# Audio.net
KiCad netlist of a schematic drawn in Altium Designer
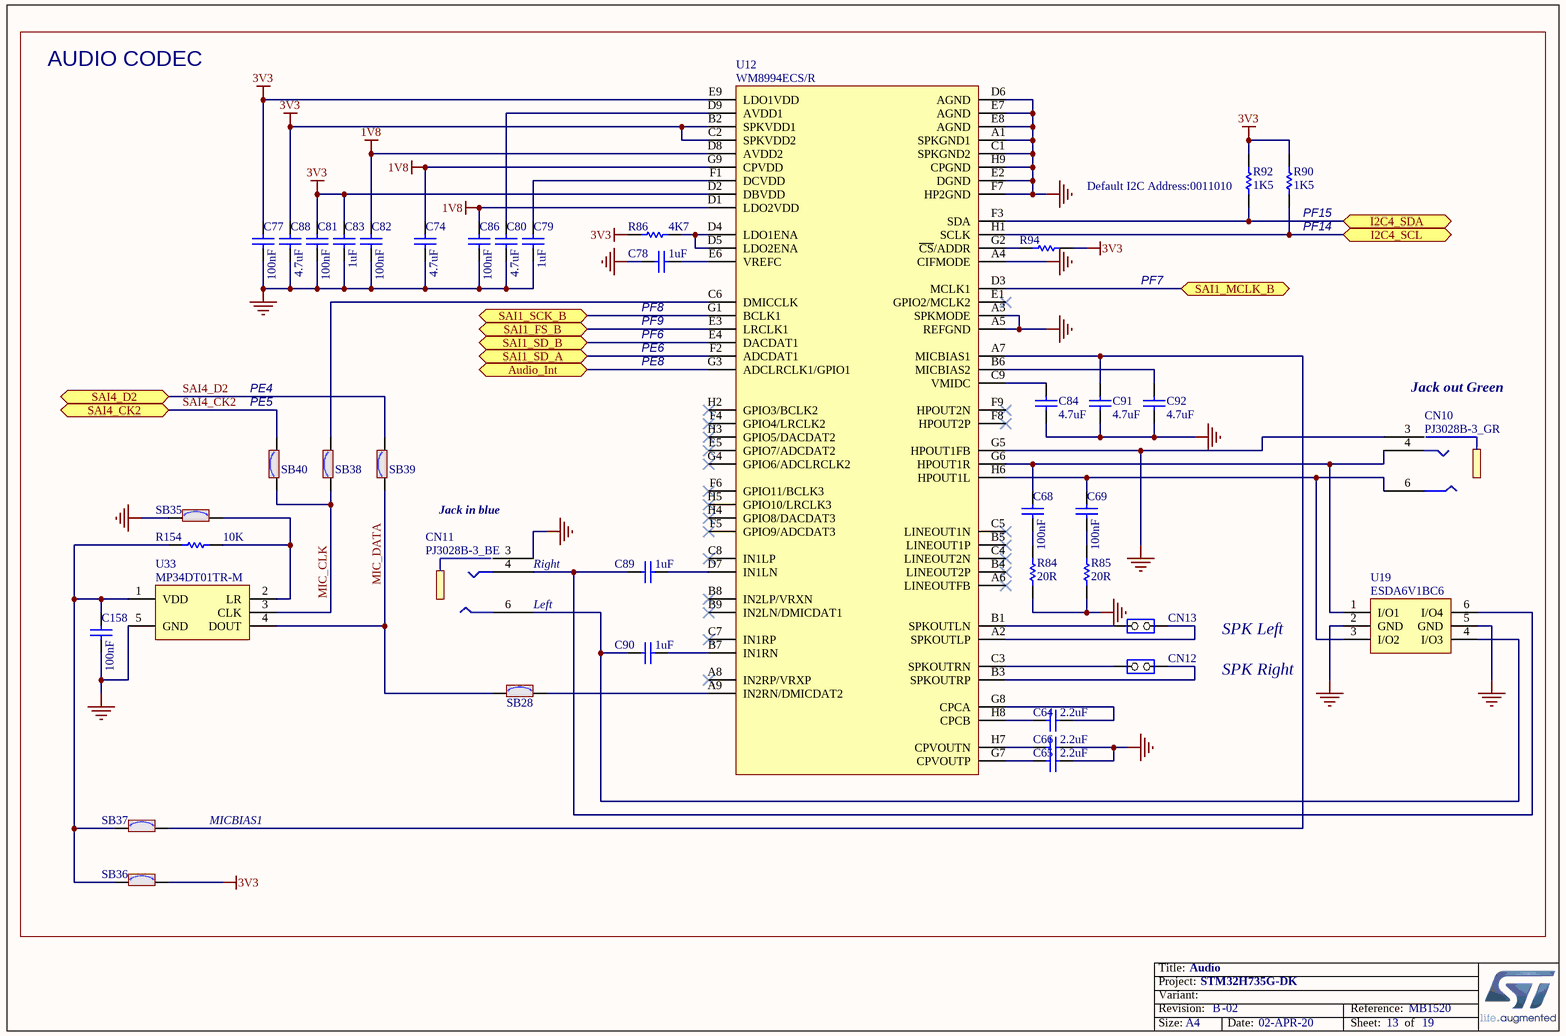
[diagram p0: Audio.SchDoc]

(export (version "E")
  (design (tool "Eeschema 10.0.6"))
  (components
    (comp (ref "C64")
      (value "2.2uF")
      (footprint "C0603")
      (description "Capacitor, MLCC, 2.2uF, 10V, X5R, 10%, 0603, T=0,8mm")
      (fields
        (field (name "INTERNAL_PART_NUMBER") "MCD-00012")
        (field (name "MANUFACTURER_PART_NUMBER") "CC0603KRX5R6BB225")
        (field (name "PROVIDED_BY") "SUBCO")
      )
      (libsource (lib "MCD_PARTS_database") (part "Capacitor"))
    )
    (comp (ref "C65")
      (value "2.2uF")
      (footprint "C0603")
      (description "Capacitor, MLCC, 2.2uF, 10V, X5R, 10%, 0603, T=0,8mm")
      (fields
        (field (name "INTERNAL_PART_NUMBER") "MCD-00012")
        (field (name "MANUFACTURER_PART_NUMBER") "CC0603KRX5R6BB225")
        (field (name "PROVIDED_BY") "SUBCO")
      )
      (libsource (lib "MCD_PARTS_database") (part "Capacitor"))
    )
    (comp (ref "C66")
      (value "2.2uF")
      (footprint "C0603")
      (description "Capacitor, MLCC, 2.2uF, 10V, X5R, 10%, 0603, T=0,8mm")
      (fields
        (field (name "INTERNAL_PART_NUMBER") "MCD-00012")
        (field (name "MANUFACTURER_PART_NUMBER") "CC0603KRX5R6BB225")
        (field (name "PROVIDED_BY") "SUBCO")
      )
      (libsource (lib "MCD_PARTS_database") (part "Capacitor"))
    )
    (comp (ref "C68")
      (value "100nF")
      (footprint "C0402")
      (description "Capacitor, MLCC, 100nF, 16V, X7R, 10%, 0402, T=0,5mm")
      (fields
        (field (name "INTERNAL_PART_NUMBER") "MCD-00102")
        (field (name "MANUFACTURER_PART_NUMBER") "CC0402KRX7R7BB104")
        (field (name "PROVIDED_BY") "SUBCO")
      )
      (libsource (lib "MCD_PARTS_database") (part "Capacitor"))
    )
    (comp (ref "C69")
      (value "100nF")
      (footprint "C0402")
      (description "Capacitor, MLCC, 100nF, 16V, X7R, 10%, 0402, T=0,5mm")
      (fields
        (field (name "INTERNAL_PART_NUMBER") "MCD-00102")
        (field (name "MANUFACTURER_PART_NUMBER") "CC0402KRX7R7BB104")
        (field (name "PROVIDED_BY") "SUBCO")
      )
      (libsource (lib "MCD_PARTS_database") (part "Capacitor"))
    )
    (comp (ref "C74")
      (value "4.7uF")
      (footprint "C0603")
      (description "Capacitor, MLCC, 4.7uF, 16V, X5R, 10%, 0603, T=0.8mm")
      (fields
        (field (name "INTERNAL_PART_NUMBER") "MCD-00009")
        (field (name "MANUFACTURER_PART_NUMBER") "CC0603KRX5R7BB475")
        (field (name "PROVIDED_BY") "SUBCO")
      )
      (libsource (lib "MCD_PARTS_database") (part "Capacitor"))
    )
    (comp (ref "C77")
      (value "100nF")
      (footprint "C0402")
      (description "Capacitor, MLCC, 100nF, 16V, X7R, 10%, 0402, T=0,5mm")
      (fields
        (field (name "INTERNAL_PART_NUMBER") "MCD-00102")
        (field (name "MANUFACTURER_PART_NUMBER") "CC0402KRX7R7BB104")
        (field (name "PROVIDED_BY") "SUBCO")
      )
      (libsource (lib "MCD_PARTS_database") (part "Capacitor"))
    )
    (comp (ref "C78")
      (value "1uF")
      (footprint "C0603")
      (description "Capacitor, MLCC, 1uF, 16V, X5R, 10%, 0603, T=0,8mm")
      (fields
        (field (name "INTERNAL_PART_NUMBER") "MCD-00010")
        (field (name "MANUFACTURER_PART_NUMBER") "CC0603KRX5R7BB105")
        (field (name "PROVIDED_BY") "SUBCO")
      )
      (libsource (lib "MCD_PARTS_database") (part "Capacitor"))
    )
    (comp (ref "C79")
      (value "1uF")
      (footprint "C0603")
      (description "Capacitor, MLCC, 1uF, 16V, X5R, 10%, 0603, T=0,8mm")
      (fields
        (field (name "INTERNAL_PART_NUMBER") "MCD-00010")
        (field (name "MANUFACTURER_PART_NUMBER") "CC0603KRX5R7BB105")
        (field (name "PROVIDED_BY") "SUBCO")
      )
      (libsource (lib "MCD_PARTS_database") (part "Capacitor"))
    )
    (comp (ref "C80")
      (value "4.7uF")
      (footprint "C0603")
      (description "Capacitor, MLCC, 4.7uF, 16V, X5R, 10%, 0603, T=0.8mm")
      (fields
        (field (name "INTERNAL_PART_NUMBER") "MCD-00009")
        (field (name "MANUFACTURER_PART_NUMBER") "CC0603KRX5R7BB475")
        (field (name "PROVIDED_BY") "SUBCO")
      )
      (libsource (lib "MCD_PARTS_database") (part "Capacitor"))
    )
    (comp (ref "C81")
      (value "100nF")
      (footprint "C0402")
      (description "Capacitor, MLCC, 100nF, 16V, X7R, 10%, 0402, T=0,5mm")
      (fields
        (field (name "INTERNAL_PART_NUMBER") "MCD-00102")
        (field (name "MANUFACTURER_PART_NUMBER") "CC0402KRX7R7BB104")
        (field (name "PROVIDED_BY") "SUBCO")
      )
      (libsource (lib "MCD_PARTS_database") (part "Capacitor"))
    )
    (comp (ref "C82")
      (value "100nF")
      (footprint "C0402")
      (description "Capacitor, MLCC, 100nF, 16V, X7R, 10%, 0402, T=0,5mm")
      (fields
        (field (name "INTERNAL_PART_NUMBER") "MCD-00102")
        (field (name "MANUFACTURER_PART_NUMBER") "CC0402KRX7R7BB104")
        (field (name "PROVIDED_BY") "SUBCO")
      )
      (libsource (lib "MCD_PARTS_database") (part "Capacitor"))
    )
    (comp (ref "C83")
      (value "1uF")
      (footprint "C0603")
      (description "Capacitor, MLCC, 1uF, 16V, X5R, 10%, 0603, T=0,8mm")
      (fields
        (field (name "INTERNAL_PART_NUMBER") "MCD-00010")
        (field (name "MANUFACTURER_PART_NUMBER") "CC0603KRX5R7BB105")
        (field (name "PROVIDED_BY") "SUBCO")
      )
      (libsource (lib "MCD_PARTS_database") (part "Capacitor"))
    )
    (comp (ref "C84")
      (value "4.7uF")
      (footprint "C0603")
      (description "Capacitor, MLCC, 4.7uF, 16V, X5R, 10%, 0603, T=0.8mm")
      (fields
        (field (name "INTERNAL_PART_NUMBER") "MCD-00009")
        (field (name "MANUFACTURER_PART_NUMBER") "CC0603KRX5R7BB475")
        (field (name "PROVIDED_BY") "SUBCO")
      )
      (libsource (lib "MCD_PARTS_database") (part "Capacitor"))
    )
    (comp (ref "C86")
      (value "100nF")
      (footprint "C0402")
      (description "Capacitor, MLCC, 100nF, 16V, X7R, 10%, 0402, T=0,5mm")
      (fields
        (field (name "INTERNAL_PART_NUMBER") "MCD-00102")
        (field (name "MANUFACTURER_PART_NUMBER") "CC0402KRX7R7BB104")
        (field (name "PROVIDED_BY") "SUBCO")
      )
      (libsource (lib "MCD_PARTS_database") (part "Capacitor"))
    )
    (comp (ref "C88")
      (value "4.7uF")
      (footprint "C0603")
      (description "Capacitor, MLCC, 4.7uF, 16V, X5R, 10%, 0603, T=0.8mm")
      (fields
        (field (name "INTERNAL_PART_NUMBER") "MCD-00009")
        (field (name "MANUFACTURER_PART_NUMBER") "CC0603KRX5R7BB475")
        (field (name "PROVIDED_BY") "SUBCO")
      )
      (libsource (lib "MCD_PARTS_database") (part "Capacitor"))
    )
    (comp (ref "C89")
      (value "1uF")
      (footprint "C0603")
      (description "Capacitor, MLCC, 1uF, 16V, X5R, 10%, 0603, T=0,8mm")
      (fields
        (field (name "INTERNAL_PART_NUMBER") "MCD-00010")
        (field (name "MANUFACTURER_PART_NUMBER") "CC0603KRX5R7BB105")
        (field (name "PROVIDED_BY") "SUBCO")
      )
      (libsource (lib "MCD_PARTS_database") (part "Capacitor"))
    )
    (comp (ref "C90")
      (value "1uF")
      (footprint "C0603")
      (description "Capacitor, MLCC, 1uF, 16V, X5R, 10%, 0603, T=0,8mm")
      (fields
        (field (name "INTERNAL_PART_NUMBER") "MCD-00010")
        (field (name "MANUFACTURER_PART_NUMBER") "CC0603KRX5R7BB105")
        (field (name "PROVIDED_BY") "SUBCO")
      )
      (libsource (lib "MCD_PARTS_database") (part "Capacitor"))
    )
    (comp (ref "C91")
      (value "4.7uF")
      (footprint "C0603")
      (description "Capacitor, MLCC, 4.7uF, 16V, X5R, 10%, 0603, T=0.8mm")
      (fields
        (field (name "INTERNAL_PART_NUMBER") "MCD-00009")
        (field (name "MANUFACTURER_PART_NUMBER") "CC0603KRX5R7BB475")
        (field (name "PROVIDED_BY") "SUBCO")
      )
      (libsource (lib "MCD_PARTS_database") (part "Capacitor"))
    )
    (comp (ref "C92")
      (value "4.7uF")
      (footprint "C0603")
      (description "Capacitor, MLCC, 4.7uF, 16V, X5R, 10%, 0603, T=0.8mm")
      (fields
        (field (name "INTERNAL_PART_NUMBER") "MCD-00009")
        (field (name "MANUFACTURER_PART_NUMBER") "CC0603KRX5R7BB475")
        (field (name "PROVIDED_BY") "SUBCO")
      )
      (libsource (lib "MCD_PARTS_database") (part "Capacitor"))
    )
    (comp (ref "C158")
      (value "100nF")
      (footprint "C0402")
      (description "Capacitor, MLCC, 100nF, 16V, X7R, 10%, 0402, T=0,5mm")
      (fields
        (field (name "INTERNAL_PART_NUMBER") "MCD-00102")
        (field (name "MANUFACTURER_PART_NUMBER") "CC0402KRX7R7BB104")
        (field (name "PROVIDED_BY") "SUBCO")
      )
      (libsource (lib "MCD_PARTS_database") (part "Capacitor"))
    )
    (comp (ref "CN10")
      (value "PJ3028B-3_GR")
      (footprint "CON_PHONE-JACK-3P5_HY_PJ3028B")
      (description "Connector Jack socket Stereo 3.5mm, 3 pins, RA, SMT, Green (Line output)")
      (fields
        (field (name "INTERNAL_PART_NUMBER") "MCD-00018")
        (field (name "MANUFACTURER") "QIAOD")
        (field (name "PROVIDED_BY") "SUBCO")
      )
      (libsource (lib "MCD_PARTS_database") (part "Jack_PJ3028B-3_3P"))
    )
    (comp (ref "CN11")
      (value "PJ3028B-3_BE")
      (footprint "CON_PHONE-JACK-3P5_HY_PJ3028B")
      (description "Connector Jack socket Stereo 3.5mm, 3 pins, RA, SMT, Blue (Line input)")
      (fields
        (field (name "INTERNAL_PART_NUMBER") "MCD-00682")
        (field (name "MANUFACTURER") "QIAOD")
        (field (name "PROVIDED_BY") "SUBCO")
      )
      (libsource (lib "") (part "Jack_PJ3028B-3_3P_1"))
    )
    (comp (ref "CN12")
      (value "Jumper_Header 2x1")
      (footprint "CON_SAMTEC_TSW-102-07-G-S")
      (description "Header, 2x1, 2,54mm, VR, TH, Height 5.84mm/2.54mm")
      (fields
        (field (name "INTERNAL_PART_NUMBER") "MCD-00045")
        (field (name "MANUFACTURER_PART_NUMBER") "TSW-102-07-x-S")
        (field (name "PROVIDED_BY") "SUBCO")
      )
      (libsource (lib "MCD_PARTS_database") (part "Jumper_Header 2x1"))
    )
    (comp (ref "CN13")
      (value "Jumper_Header 2x1")
      (footprint "CON_SAMTEC_TSW-102-07-G-S")
      (description "Header, 2x1, 2,54mm, VR, TH, Height 5.84mm/2.54mm")
      (fields
        (field (name "INTERNAL_PART_NUMBER") "MCD-00045")
        (field (name "MANUFACTURER_PART_NUMBER") "TSW-102-07-x-S")
        (field (name "PROVIDED_BY") "SUBCO")
      )
      (libsource (lib "MCD_PARTS_database") (part "Jumper_Header 2x1"))
    )
    (comp (ref "R84")
      (value "20R")
      (footprint "R0603")
      (description "Resistor,20R,0603,1%,1/10W")
      (fields
        (field (name "INTERNAL_PART_NUMBER") "MCD-00345")
        (field (name "MANUFACTURER_PART_NUMBER") "RC0603FR-0720RL")
        (field (name "PROVIDED_BY") "SUBCO")
      )
      (libsource (lib "MCD_PARTS_database") (part "Resistor"))
    )
    (comp (ref "R85")
      (value "20R")
      (footprint "R0603")
      (description "Resistor,20R,0603,1%,1/10W")
      (fields
        (field (name "INTERNAL_PART_NUMBER") "MCD-00345")
        (field (name "MANUFACTURER_PART_NUMBER") "RC0603FR-0720RL")
        (field (name "PROVIDED_BY") "SUBCO")
      )
      (libsource (lib "MCD_PARTS_database") (part "Resistor"))
    )
    (comp (ref "R86")
      (value "4K7")
      (footprint "R0603")
      (description "Resistor,4K7,0603,1%,1/10W")
      (fields
        (field (name "INTERNAL_PART_NUMBER") "MCD-00219")
        (field (name "MANUFACTURER_PART_NUMBER") "RC0603FR-074K7L")
        (field (name "PROVIDED_BY") "SUBCO")
      )
      (libsource (lib "MCD_PARTS_database") (part "Resistor"))
    )
    (comp (ref "R90")
      (value "1K5")
      (footprint "R0402")
      (description "Resistor,1K5,0402,1%,1/16W")
      (fields
        (field (name "INTERNAL_PART_NUMBER") "MCD-00068")
        (field (name "MANUFACTURER_PART_NUMBER") "RC0402FR-071K5L")
        (field (name "PROVIDED_BY") "SUBCO")
      )
      (libsource (lib "MCD_PARTS_database") (part "Resistor"))
    )
    (comp (ref "R92")
      (value "1K5")
      (footprint "R0402")
      (description "Resistor,1K5,0402,1%,1/16W")
      (fields
        (field (name "INTERNAL_PART_NUMBER") "MCD-00068")
        (field (name "MANUFACTURER_PART_NUMBER") "RC0402FR-071K5L")
        (field (name "PROVIDED_BY") "SUBCO")
      )
      (libsource (lib "MCD_PARTS_database") (part "Resistor"))
    )
    (comp (ref "R94")
      (value "Resistor")
      (footprint "R0402")
      (description "Resistor,10K,0402,1%,1/16W")
      (fields
        (field (name "INTERNAL_PART_NUMBER") "MCD-00053")
        (field (name "MANUFACTURER_PART_NUMBER") "RC0402FR-0710KL")
        (field (name "PROVIDED_BY") "SUBCO")
      )
      (libsource (lib "MCD_PARTS_database") (part "Resistor"))
    )
    (comp (ref "R154")
      (value "10K")
      (footprint "R0402")
      (description "Resistor,10K,0402,1%,1/16W")
      (fields
        (field (name "INTERNAL_PART_NUMBER") "MCD-00053")
        (field (name "MANUFACTURER_PART_NUMBER") "RC0402FR-0710KL")
        (field (name "PROVIDED_BY") "SUBCO")
      )
      (libsource (lib "MCD_PARTS_database") (part "Resistor"))
    )
    (comp (ref "SB28")
      (value "SB_ON")
      (footprint "SOLDER-BRIDGE_R0603-0R")
      (description "Solder Bridge ON")
      (fields
        (field (name "INTERNAL_PART_NUMBER") "MCD-00071")
        (field (name "MANUFACTURER_PART_NUMBER") "RC0603JR-070RL")
        (field (name "PROVIDED_BY") "SUBCO")
      )
      (libsource (lib "MCD_PARTS_database") (part "SB_ON"))
    )
    (comp (ref "SB35")
      (value "SB_ON")
      (footprint "SOLDER-BRIDGE_R0603-0R")
      (description "Solder Bridge ON")
      (fields
        (field (name "INTERNAL_PART_NUMBER") "MCD-00071")
        (field (name "MANUFACTURER_PART_NUMBER") "RC0603JR-070RL")
        (field (name "PROVIDED_BY") "SUBCO")
      )
      (libsource (lib "MCD_PARTS_database") (part "SB_ON"))
    )
    (comp (ref "SB36")
      (value "SB_ON")
      (footprint "SOLDER-BRIDGE_R0603-0R")
      (description "Solder Bridge ON")
      (fields
        (field (name "INTERNAL_PART_NUMBER") "MCD-00071")
        (field (name "MANUFACTURER_PART_NUMBER") "RC0603JR-070RL")
        (field (name "PROVIDED_BY") "SUBCO")
      )
      (libsource (lib "MCD_PARTS_database") (part "SB_ON"))
    )
    (comp (ref "SB37")
      (value "SB_ON")
      (footprint "SOLDER-BRIDGE_R0603-0R")
      (description "Solder Bridge ON")
      (fields
        (field (name "INTERNAL_PART_NUMBER") "MCD-00071")
        (field (name "MANUFACTURER_PART_NUMBER") "RC0603JR-070RL")
        (field (name "PROVIDED_BY") "SUBCO")
      )
      (libsource (lib "MCD_PARTS_database") (part "SB_ON"))
    )
    (comp (ref "SB38")
      (value "SB_ON")
      (footprint "SOLDER-BRIDGE_R0603-0R")
      (description "Solder Bridge ON")
      (fields
        (field (name "INTERNAL_PART_NUMBER") "MCD-00071")
        (field (name "MANUFACTURER_PART_NUMBER") "RC0603JR-070RL")
        (field (name "PROVIDED_BY") "SUBCO")
      )
      (libsource (lib "") (part "SB_ON_1"))
    )
    (comp (ref "SB39")
      (value "SB_ON")
      (footprint "SOLDER-BRIDGE_R0603-0R")
      (description "Solder Bridge ON")
      (fields
        (field (name "INTERNAL_PART_NUMBER") "MCD-00071")
        (field (name "MANUFACTURER_PART_NUMBER") "RC0603JR-070RL")
        (field (name "PROVIDED_BY") "SUBCO")
      )
      (libsource (lib "") (part "SB_ON_1"))
    )
    (comp (ref "SB40")
      (value "SB_ON")
      (footprint "SOLDER-BRIDGE_R0603-0R")
      (description "Solder Bridge ON")
      (fields
        (field (name "INTERNAL_PART_NUMBER") "MCD-00071")
        (field (name "MANUFACTURER_PART_NUMBER") "RC0603JR-070RL")
        (field (name "PROVIDED_BY") "SUBCO")
      )
      (libsource (lib "") (part "SB_ON_1"))
    )
    (comp (ref "U12")
      (value "WM8994ECS/R")
      (footprint "ICC_W-CSP-BGA72_4P511X4P023_P050")
      (description "Multi-Channel Audio Hub CODEC for Smartphones")
      (fields
        (field (name "INTERNAL_PART_NUMBER") "MCD-00079")
        (field (name "MANUFACTURER") "CIRRUS LOGIC")
        (field (name "PROVIDED_BY") "SUBCO")
      )
      (libsource (lib "MCD_PARTS_database") (part "WM8994ECS/R"))
    )
    (comp (ref "U19")
      (value "ESDA6V1BC6")
      (footprint "ESD_SOT23-6L")
      (description "Quad Bidir ESD protection")
      (fields
        (field (name "INTERNAL_PART_NUMBER") "MCD-00247")
        (field (name "MANUFACTURER") "STMICROELECTRONICS")
        (field (name "PROVIDED_BY") "SUBCO with ST control")
      )
      (libsource (lib "MCD_PARTS_database") (part "ESDA6V1BC6"))
    )
    (comp (ref "U33")
      (value "MP34DT01TR-M")
      (footprint "MIC_HCLGA_3X4X1_4LD")
      (description "MEMS audio sensor, omnidirectional digital microphone")
      (fields
        (field (name "INTERNAL_PART_NUMBER") "MCD-00081")
        (field (name "MANUFACTURER") "STMICROELECTRONICS")
        (field (name "PROVIDED_BY") "SUBCO with ST control")
      )
      (libsource (lib "MCD_PARTS_database") (part "MP34DT01TR-M"))
    )
  )
  (nets
    (net (code "1") (name "/Audio_Int") (class "Default")
      (node (ref "U12") (pin "G3") (pinfunction "ADCLRCLK1/GPIO1_G3") (pintype "passive"))
    )
    (net (code "2") (name "/I2C4_SCL") (class "Default")
      (node (ref "R90") (pin "1") (pinfunction "1_1") (pintype "passive"))
      (node (ref "U12") (pin "H1") (pinfunction "SCLK_H1") (pintype "passive"))
    )
    (net (code "3") (name "/I2C4_SDA") (class "Default")
      (node (ref "R92") (pin "1") (pinfunction "1_1") (pintype "passive"))
      (node (ref "U12") (pin "F3") (pinfunction "SDA_F3") (pintype "passive"))
    )
    (net (code "4") (name "/MIC_CLK") (class "Default")
      (node (ref "SB38") (pin "1") (pinfunction "1_1") (pintype "passive"))
      (node (ref "SB40") (pin "1") (pinfunction "1_1") (pintype "passive"))
      (node (ref "U33") (pin "3") (pinfunction "CLK_3") (pintype "passive"))
    )
    (net (code "5") (name "/MIC_DATA") (class "Default")
      (node (ref "SB28") (pin "1") (pinfunction "1_1") (pintype "passive"))
      (node (ref "SB39") (pin "1") (pinfunction "1_1") (pintype "passive"))
      (node (ref "U33") (pin "4") (pinfunction "DOUT_4") (pintype "passive"))
    )
    (net (code "6") (name "/SAI1_FS_B") (class "Default")
      (node (ref "U12") (pin "E3") (pinfunction "LRCLK1_E3") (pintype "passive"))
    )
    (net (code "7") (name "/SAI1_MCLK_B") (class "Default")
      (node (ref "U12") (pin "D3") (pinfunction "MCLK1_D3") (pintype "passive"))
    )
    (net (code "8") (name "/SAI1_SCK_B") (class "Default")
      (node (ref "U12") (pin "G1") (pinfunction "BCLK1_G1") (pintype "passive"))
    )
    (net (code "9") (name "/SAI1_SD_A") (class "Default")
      (node (ref "U12") (pin "F2") (pinfunction "ADCDAT1_F2") (pintype "passive"))
    )
    (net (code "10") (name "/SAI1_SD_B") (class "Default")
      (node (ref "U12") (pin "E4") (pinfunction "DACDAT1_E4") (pintype "passive"))
    )
    (net (code "11") (name "/SAI4_CK2") (class "Default")
      (node (ref "SB40") (pin "2") (pinfunction "2_2") (pintype "passive"))
    )
    (net (code "12") (name "/SAI4_D2") (class "Default")
      (node (ref "SB39") (pin "2") (pinfunction "2_2") (pintype "passive"))
    )
    (net (code "13") (name "1V8") (class "Default")
      (node (ref "C74") (pin "2") (pinfunction "2_2") (pintype "passive"))
      (node (ref "C82") (pin "1") (pinfunction "1_1") (pintype "passive"))
      (node (ref "C86") (pin "1") (pinfunction "1_1") (pintype "passive"))
      (node (ref "U12") (pin "D1") (pinfunction "LDO2VDD_D1") (pintype "passive"))
      (node (ref "U12") (pin "D8") (pinfunction "AVDD2_D8") (pintype "passive"))
      (node (ref "U12") (pin "G9") (pinfunction "CPVDD_G9") (pintype "passive"))
    )
    (net (code "14") (name "3V3") (class "Default")
      (node (ref "C77") (pin "1") (pinfunction "1_1") (pintype "passive"))
      (node (ref "C81") (pin "1") (pinfunction "1_1") (pintype "passive"))
      (node (ref "C83") (pin "2") (pinfunction "2_2") (pintype "passive"))
      (node (ref "C88") (pin "2") (pinfunction "2_2") (pintype "passive"))
      (node (ref "R86") (pin "1") (pinfunction "1_1") (pintype "passive"))
      (node (ref "R90") (pin "2") (pinfunction "2_2") (pintype "passive"))
      (node (ref "R92") (pin "2") (pinfunction "2_2") (pintype "passive"))
      (node (ref "R94") (pin "1") (pinfunction "1_1") (pintype "passive"))
      (node (ref "SB36") (pin "2") (pinfunction "2_2") (pintype "passive"))
      (node (ref "U12") (pin "B2") (pinfunction "SPKVDD1_B2") (pintype "passive"))
      (node (ref "U12") (pin "C2") (pinfunction "SPKVDD2_C2") (pintype "passive"))
      (node (ref "U12") (pin "D2") (pinfunction "DBVDD_D2") (pintype "passive"))
      (node (ref "U12") (pin "E9") (pinfunction "LDO1VDD_E9") (pintype "passive"))
    )
    (net (code "15") (name "GND") (class "Default")
      (node (ref "C158") (pin "2") (pinfunction "2_2") (pintype "passive"))
      (node (ref "C65") (pin "1") (pinfunction "1_1") (pintype "passive"))
      (node (ref "C66") (pin "1") (pinfunction "1_1") (pintype "passive"))
      (node (ref "C74") (pin "1") (pinfunction "1_1") (pintype "passive"))
      (node (ref "C77") (pin "2") (pinfunction "2_2") (pintype "passive"))
      (node (ref "C78") (pin "2") (pinfunction "2_2") (pintype "passive"))
      (node (ref "C79") (pin "1") (pinfunction "1_1") (pintype "passive"))
      (node (ref "C80") (pin "1") (pinfunction "1_1") (pintype "passive"))
      (node (ref "C81") (pin "2") (pinfunction "2_2") (pintype "passive"))
      (node (ref "C82") (pin "2") (pinfunction "2_2") (pintype "passive"))
      (node (ref "C83") (pin "1") (pinfunction "1_1") (pintype "passive"))
      (node (ref "C84") (pin "1") (pinfunction "1_1") (pintype "passive"))
      (node (ref "C86") (pin "2") (pinfunction "2_2") (pintype "passive"))
      (node (ref "C88") (pin "1") (pinfunction "1_1") (pintype "passive"))
      (node (ref "C91") (pin "1") (pinfunction "1_1") (pintype "passive"))
      (node (ref "C92") (pin "1") (pinfunction "1_1") (pintype "passive"))
      (node (ref "CN10") (pin "3") (pintype "passive"))
      (node (ref "CN11") (pin "3") (pintype "passive"))
      (node (ref "R84") (pin "1") (pinfunction "1_1") (pintype "passive"))
      (node (ref "R85") (pin "1") (pinfunction "1_1") (pintype "passive"))
      (node (ref "SB35") (pin "1") (pinfunction "1_1") (pintype "passive"))
      (node (ref "U12") (pin "A1") (pinfunction "SPKGND1_A1") (pintype "passive"))
      (node (ref "U12") (pin "A3") (pinfunction "SPKMODE_A3") (pintype "passive"))
      (node (ref "U12") (pin "A4") (pinfunction "CIFMODE_A4") (pintype "passive"))
      (node (ref "U12") (pin "A5") (pinfunction "REFGND_A5") (pintype "passive"))
      (node (ref "U12") (pin "C1") (pinfunction "SPKGND2_C1") (pintype "passive"))
      (node (ref "U12") (pin "D6") (pinfunction "AGND_D6") (pintype "passive"))
      (node (ref "U12") (pin "E2") (pinfunction "DGND_E2") (pintype "passive"))
      (node (ref "U12") (pin "E7") (pinfunction "AGND_E7") (pintype "passive"))
      (node (ref "U12") (pin "E8") (pinfunction "AGND_E8") (pintype "passive"))
      (node (ref "U12") (pin "F7") (pinfunction "HP2GND_F7") (pintype "passive"))
      (node (ref "U12") (pin "G5") (pinfunction "HPOUT1FB_G5") (pintype "passive"))
      (node (ref "U12") (pin "H9") (pinfunction "CPGND_H9") (pintype "passive"))
      (node (ref "U19") (pin "2") (pinfunction "GND_2") (pintype "passive"))
      (node (ref "U19") (pin "5") (pinfunction "GND_5") (pintype "passive"))
      (node (ref "U33") (pin "5") (pinfunction "GND_5") (pintype "passive"))
    )
    (net (code "16") (name "Net-(C68-Pad2)") (class "Default")
      (node (ref "C68") (pin "2") (pinfunction "2_2") (pintype "passive"))
      (node (ref "R84") (pin "2") (pinfunction "2_2") (pintype "passive"))
    )
    (net (code "17") (name "Net-(C69-Pad2)") (class "Default")
      (node (ref "C69") (pin "2") (pinfunction "2_2") (pintype "passive"))
      (node (ref "R85") (pin "2") (pinfunction "2_2") (pintype "passive"))
    )
    (net (code "18") (name "Net-(CN12-COMMON)") (class "Default")
      (node (ref "CN12") (pin "1") (pinfunction "COMMON_1") (pintype "passive"))
      (node (ref "U12") (pin "B3") (pinfunction "SPKOUTRP_B3") (pintype "passive"))
    )
    (net (code "19") (name "Net-(CN12-NO)") (class "Default")
      (node (ref "CN12") (pin "2") (pinfunction "NO_2") (pintype "passive"))
      (node (ref "U12") (pin "C3") (pinfunction "SPKOUTRN_C3") (pintype "passive"))
    )
    (net (code "20") (name "Net-(CN13-COMMON)") (class "Default")
      (node (ref "CN13") (pin "1") (pinfunction "COMMON_1") (pintype "passive"))
      (node (ref "U12") (pin "A2") (pinfunction "SPKOUTLP_A2") (pintype "passive"))
    )
    (net (code "21") (name "Net-(CN13-NO)") (class "Default")
      (node (ref "CN13") (pin "2") (pinfunction "NO_2") (pintype "passive"))
      (node (ref "U12") (pin "B1") (pinfunction "SPKOUTLN_B1") (pintype "passive"))
    )
    (net (code "22") (name "Net-(U12-AVDD1)") (class "Default")
      (node (ref "C80") (pin "2") (pinfunction "2_2") (pintype "passive"))
      (node (ref "U12") (pin "D9") (pinfunction "AVDD1_D9") (pintype "passive"))
    )
    (net (code "23") (name "Net-(U12-CPCA)") (class "Default")
      (node (ref "C64") (pin "1") (pinfunction "1_1") (pintype "passive"))
      (node (ref "U12") (pin "G8") (pinfunction "CPCA_G8") (pintype "passive"))
    )
    (net (code "24") (name "Net-(U12-CPCB)") (class "Default")
      (node (ref "C64") (pin "2") (pinfunction "2_2") (pintype "passive"))
      (node (ref "U12") (pin "H8") (pinfunction "CPCB_H8") (pintype "passive"))
    )
    (net (code "25") (name "Net-(U12-CPVOUTN)") (class "Default")
      (node (ref "C66") (pin "2") (pinfunction "2_2") (pintype "passive"))
      (node (ref "U12") (pin "H7") (pinfunction "CPVOUTN_H7") (pintype "passive"))
    )
    (net (code "26") (name "Net-(U12-CPVOUTP)") (class "Default")
      (node (ref "C65") (pin "2") (pinfunction "2_2") (pintype "passive"))
      (node (ref "U12") (pin "G7") (pinfunction "CPVOUTP_G7") (pintype "passive"))
    )
    (net (code "27") (name "Net-(U12-DCVDD)") (class "Default")
      (node (ref "C79") (pin "2") (pinfunction "2_2") (pintype "passive"))
      (node (ref "U12") (pin "F1") (pinfunction "DCVDD_F1") (pintype "passive"))
    )
    (net (code "28") (name "Net-(U12-DMICCLK)") (class "Default")
      (node (ref "SB38") (pin "2") (pinfunction "2_2") (pintype "passive"))
      (node (ref "U12") (pin "C6") (pinfunction "DMICCLK_C6") (pintype "passive"))
    )
    (net (code "29") (name "Net-(U12-HPOUT1L)") (class "Default")
      (node (ref "C69") (pin "1") (pinfunction "1_1") (pintype "passive"))
      (node (ref "CN10") (pin "6") (pintype "passive"))
      (node (ref "U12") (pin "H6") (pinfunction "HPOUT1L_H6") (pintype "passive"))
      (node (ref "U19") (pin "3") (pinfunction "I/O2_3") (pintype "passive"))
    )
    (net (code "30") (name "Net-(U12-HPOUT1R)") (class "Default")
      (node (ref "C68") (pin "1") (pinfunction "1_1") (pintype "passive"))
      (node (ref "CN10") (pin "4") (pintype "passive"))
      (node (ref "U12") (pin "G6") (pinfunction "HPOUT1R_G6") (pintype "passive"))
      (node (ref "U19") (pin "1") (pinfunction "I/O1_1") (pintype "passive"))
    )
    (net (code "31") (name "Net-(U12-IN1LN)") (class "Default")
      (node (ref "C89") (pin "1") (pinfunction "1_1") (pintype "passive"))
      (node (ref "U12") (pin "D7") (pinfunction "IN1LN_D7") (pintype "passive"))
    )
    (net (code "32") (name "Net-(U12-IN1RN)") (class "Default")
      (node (ref "C90") (pin "1") (pinfunction "1_1") (pintype "passive"))
      (node (ref "U12") (pin "B7") (pinfunction "IN1RN_B7") (pintype "passive"))
    )
    (net (code "33") (name "Net-(U12-IN2RN{slash}DMICDAT2)") (class "Default")
      (node (ref "SB28") (pin "2") (pinfunction "2_2") (pintype "passive"))
      (node (ref "U12") (pin "A9") (pinfunction "IN2RN/DMICDAT2_A9") (pintype "passive"))
    )
    (net (code "34") (name "Net-(U12-LDO1ENA)") (class "Default")
      (node (ref "R86") (pin "2") (pinfunction "2_2") (pintype "passive"))
      (node (ref "U12") (pin "D4") (pinfunction "LDO1ENA_D4") (pintype "passive"))
      (node (ref "U12") (pin "D5") (pinfunction "LDO2ENA_D5") (pintype "passive"))
    )
    (net (code "35") (name "Net-(U12-MICBIAS1)") (class "Default")
      (node (ref "C91") (pin "2") (pinfunction "2_2") (pintype "passive"))
      (node (ref "SB37") (pin "2") (pinfunction "2_2") (pintype "passive"))
      (node (ref "U12") (pin "A7") (pinfunction "MICBIAS1_A7") (pintype "passive"))
    )
    (net (code "36") (name "Net-(U12-MICBIAS2)") (class "Default")
      (node (ref "C92") (pin "2") (pinfunction "2_2") (pintype "passive"))
      (node (ref "U12") (pin "B6") (pinfunction "MICBIAS2_B6") (pintype "passive"))
    )
    (net (code "37") (name "Net-(U12-VMIDC)") (class "Default")
      (node (ref "C84") (pin "2") (pinfunction "2_2") (pintype "passive"))
      (node (ref "U12") (pin "C9") (pinfunction "VMIDC_C9") (pintype "passive"))
    )
    (net (code "38") (name "Net-(U12-VREFC)") (class "Default")
      (node (ref "C78") (pin "1") (pinfunction "1_1") (pintype "passive"))
      (node (ref "U12") (pin "E6") (pinfunction "VREFC_E6") (pintype "passive"))
    )
    (net (code "39") (name "Net-(U12-~{CS}{slash}ADDR)") (class "Default")
      (node (ref "R94") (pin "2") (pinfunction "2_2") (pintype "passive"))
      (node (ref "U12") (pin "G2") (pinfunction "~{CS}/ADDR_G2") (pintype "passive"))
    )
    (net (code "40") (name "Net-(U19-I{slash}O3)") (class "Default")
      (node (ref "C90") (pin "2") (pinfunction "2_2") (pintype "passive"))
      (node (ref "CN11") (pin "6") (pintype "passive"))
      (node (ref "U19") (pin "4") (pinfunction "I/O3_4") (pintype "passive"))
    )
    (net (code "41") (name "Net-(U19-I{slash}O4)") (class "Default")
      (node (ref "C89") (pin "2") (pinfunction "2_2") (pintype "passive"))
      (node (ref "CN11") (pin "4") (pintype "passive"))
      (node (ref "U19") (pin "6") (pinfunction "I/O4_6") (pintype "passive"))
    )
    (net (code "42") (name "Net-(U33-LR)") (class "Default")
      (node (ref "R154") (pin "1") (pinfunction "1_1") (pintype "passive"))
      (node (ref "SB35") (pin "2") (pinfunction "2_2") (pintype "passive"))
      (node (ref "U33") (pin "2") (pinfunction "LR_2") (pintype "passive"))
    )
    (net (code "43") (name "Net-(U33-VDD)") (class "Default")
      (node (ref "C158") (pin "1") (pinfunction "1_1") (pintype "passive"))
      (node (ref "R154") (pin "2") (pinfunction "2_2") (pintype "passive"))
      (node (ref "SB36") (pin "1") (pinfunction "1_1") (pintype "passive"))
      (node (ref "SB37") (pin "1") (pinfunction "1_1") (pintype "passive"))
      (node (ref "U33") (pin "1") (pinfunction "VDD_1") (pintype "passive"))
    )
    (net (code "44") (name "unconnected-(U12-GPIO2{slash}MCLK2-PadE1)") (class "Default")
      (node (ref "U12") (pin "E1") (pinfunction "GPIO2/MCLK2_E1") (pintype "passive+no_connect"))
    )
    (net (code "45") (name "unconnected-(U12-GPIO3{slash}BCLK2-PadH2)") (class "Default")
      (node (ref "U12") (pin "H2") (pinfunction "GPIO3/BCLK2_H2") (pintype "passive+no_connect"))
    )
    (net (code "46") (name "unconnected-(U12-GPIO4{slash}LRCLK2-PadF4)") (class "Default")
      (node (ref "U12") (pin "F4") (pinfunction "GPIO4/LRCLK2_F4") (pintype "passive+no_connect"))
    )
    (net (code "47") (name "unconnected-(U12-GPIO5{slash}DACDAT2-PadH3)") (class "Default")
      (node (ref "U12") (pin "H3") (pinfunction "GPIO5/DACDAT2_H3") (pintype "passive+no_connect"))
    )
    (net (code "48") (name "unconnected-(U12-GPIO6{slash}ADCLRCLK2-PadG4)") (class "Default")
      (node (ref "U12") (pin "G4") (pinfunction "GPIO6/ADCLRCLK2_G4") (pintype "passive+no_connect"))
    )
    (net (code "49") (name "unconnected-(U12-GPIO7{slash}ADCDAT2-PadE5)") (class "Default")
      (node (ref "U12") (pin "E5") (pinfunction "GPIO7/ADCDAT2_E5") (pintype "passive+no_connect"))
    )
    (net (code "50") (name "unconnected-(U12-GPIO8{slash}DACDAT3-PadH4)") (class "Default")
      (node (ref "U12") (pin "H4") (pinfunction "GPIO8/DACDAT3_H4") (pintype "passive+no_connect"))
    )
    (net (code "51") (name "unconnected-(U12-GPIO9{slash}ADCDAT3-PadF5)") (class "Default")
      (node (ref "U12") (pin "F5") (pinfunction "GPIO9/ADCDAT3_F5") (pintype "passive+no_connect"))
    )
    (net (code "52") (name "unconnected-(U12-GPIO10{slash}LRCLK3-PadH5)") (class "Default")
      (node (ref "U12") (pin "H5") (pinfunction "GPIO10/LRCLK3_H5") (pintype "passive+no_connect"))
    )
    (net (code "53") (name "unconnected-(U12-GPIO11{slash}BCLK3-PadF6)") (class "Default")
      (node (ref "U12") (pin "F6") (pinfunction "GPIO11/BCLK3_F6") (pintype "passive+no_connect"))
    )
    (net (code "54") (name "unconnected-(U12-HPOUT2N-PadF9)") (class "Default")
      (node (ref "U12") (pin "F9") (pinfunction "HPOUT2N_F9") (pintype "passive+no_connect"))
    )
    (net (code "55") (name "unconnected-(U12-HPOUT2P-PadF8)") (class "Default")
      (node (ref "U12") (pin "F8") (pinfunction "HPOUT2P_F8") (pintype "passive+no_connect"))
    )
    (net (code "56") (name "unconnected-(U12-IN1LP-PadC8)") (class "Default")
      (node (ref "U12") (pin "C8") (pinfunction "IN1LP_C8") (pintype "passive+no_connect"))
    )
    (net (code "57") (name "unconnected-(U12-IN1RP-PadC7)") (class "Default")
      (node (ref "U12") (pin "C7") (pinfunction "IN1RP_C7") (pintype "passive+no_connect"))
    )
    (net (code "58") (name "unconnected-(U12-IN2LN{slash}DMICDAT1-PadB9)") (class "Default")
      (node (ref "U12") (pin "B9") (pinfunction "IN2LN/DMICDAT1_B9") (pintype "passive+no_connect"))
    )
    (net (code "59") (name "unconnected-(U12-IN2LP{slash}VRXN-PadB8)") (class "Default")
      (node (ref "U12") (pin "B8") (pinfunction "IN2LP/VRXN_B8") (pintype "passive+no_connect"))
    )
    (net (code "60") (name "unconnected-(U12-IN2RP{slash}VRXP-PadA8)") (class "Default")
      (node (ref "U12") (pin "A8") (pinfunction "IN2RP/VRXP_A8") (pintype "passive+no_connect"))
    )
    (net (code "61") (name "unconnected-(U12-LINEOUT1N-PadC5)") (class "Default")
      (node (ref "U12") (pin "C5") (pinfunction "LINEOUT1N_C5") (pintype "passive+no_connect"))
    )
    (net (code "62") (name "unconnected-(U12-LINEOUT1P-PadB5)") (class "Default")
      (node (ref "U12") (pin "B5") (pinfunction "LINEOUT1P_B5") (pintype "passive+no_connect"))
    )
    (net (code "63") (name "unconnected-(U12-LINEOUT2N-PadC4)") (class "Default")
      (node (ref "U12") (pin "C4") (pinfunction "LINEOUT2N_C4") (pintype "passive+no_connect"))
    )
    (net (code "64") (name "unconnected-(U12-LINEOUT2P-PadB4)") (class "Default")
      (node (ref "U12") (pin "B4") (pinfunction "LINEOUT2P_B4") (pintype "passive+no_connect"))
    )
    (net (code "65") (name "unconnected-(U12-LINEOUTFB-PadA6)") (class "Default")
      (node (ref "U12") (pin "A6") (pinfunction "LINEOUTFB_A6") (pintype "passive+no_connect"))
    )
  )
)
